# Flex_debugging.net
KiCad netlist of a schematic drawn in Altium Designer
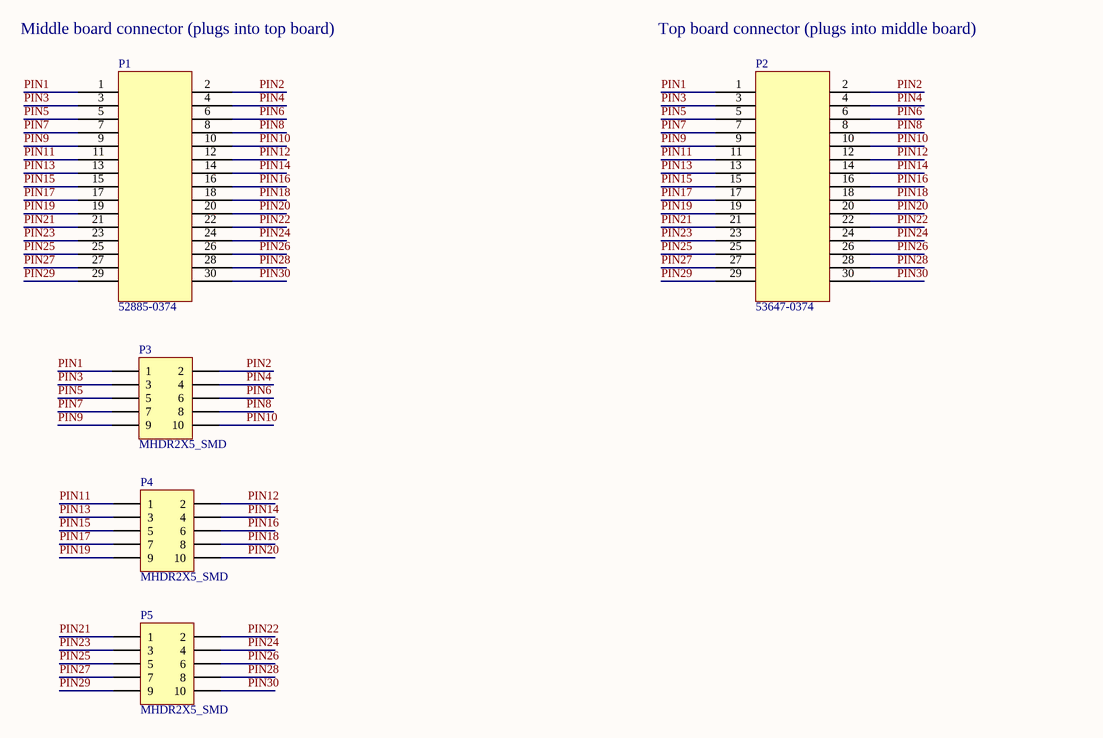
[diagram p0: Flex_debugging.SchDoc]

(export (version "E")
  (design (tool "Eeschema 10.0.6"))
  (components
    (comp (ref "P1")
      (value "52885-0374")
      (footprint "molex_52885-0374")
      (description "Molex 30-pin 0.635mm pitch receptacle connector")
      (libsource (lib "Hello") (part "molex_52885-0374"))
    )
    (comp (ref "P2")
      (value "53647-0374")
      (footprint "molex_53647-0374")
      (description "Molex 30-pin 0.635mm pitch plug connector")
      (libsource (lib "Hello") (part "molex_53647-0374"))
    )
    (comp (ref "P3")
      (value "MHDR2X5_SMD")
      (footprint "MHDR2X5_SMD")
      (description "Header, 10-Pin, Dual row SMD")
      (libsource (lib "Hello") (part "MHDR2X5_SMD"))
    )
    (comp (ref "P4")
      (value "MHDR2X5_SMD")
      (footprint "MHDR2X5_SMD")
      (description "Header, 10-Pin, Dual row SMD")
      (libsource (lib "Hello") (part "MHDR2X5_SMD"))
    )
    (comp (ref "P5")
      (value "MHDR2X5_SMD")
      (footprint "MHDR2X5_SMD")
      (description "Header, 10-Pin, Dual row SMD")
      (libsource (lib "Hello") (part "MHDR2X5_SMD"))
    )
  )
  (nets
    (net (code "1") (name "/PIN1") (class "Default")
      (node (ref "P1") (pin "1") (pintype "passive"))
      (node (ref "P2") (pin "1") (pintype "passive"))
      (node (ref "P3") (pin "1") (pinfunction "1_1") (pintype "passive"))
    )
    (net (code "2") (name "/PIN2") (class "Default")
      (node (ref "P1") (pin "2") (pintype "passive"))
      (node (ref "P2") (pin "2") (pintype "passive"))
      (node (ref "P3") (pin "2") (pinfunction "2_2") (pintype "passive"))
    )
    (net (code "3") (name "/PIN3") (class "Default")
      (node (ref "P1") (pin "3") (pintype "passive"))
      (node (ref "P2") (pin "3") (pintype "passive"))
      (node (ref "P3") (pin "3") (pinfunction "3_3") (pintype "passive"))
    )
    (net (code "4") (name "/PIN4") (class "Default")
      (node (ref "P1") (pin "4") (pintype "passive"))
      (node (ref "P2") (pin "4") (pintype "passive"))
      (node (ref "P3") (pin "4") (pinfunction "4_4") (pintype "passive"))
    )
    (net (code "5") (name "/PIN5") (class "Default")
      (node (ref "P1") (pin "5") (pintype "passive"))
      (node (ref "P2") (pin "5") (pintype "passive"))
      (node (ref "P3") (pin "5") (pinfunction "5_5") (pintype "passive"))
    )
    (net (code "6") (name "/PIN6") (class "Default")
      (node (ref "P1") (pin "6") (pintype "passive"))
      (node (ref "P2") (pin "6") (pintype "passive"))
      (node (ref "P3") (pin "6") (pinfunction "6_6") (pintype "passive"))
    )
    (net (code "7") (name "/PIN7") (class "Default")
      (node (ref "P1") (pin "7") (pintype "passive"))
      (node (ref "P2") (pin "7") (pintype "passive"))
      (node (ref "P3") (pin "7") (pinfunction "7_7") (pintype "passive"))
    )
    (net (code "8") (name "/PIN8") (class "Default")
      (node (ref "P1") (pin "8") (pintype "passive"))
      (node (ref "P2") (pin "8") (pintype "passive"))
      (node (ref "P3") (pin "8") (pinfunction "8_8") (pintype "passive"))
    )
    (net (code "9") (name "/PIN9") (class "Default")
      (node (ref "P1") (pin "9") (pintype "passive"))
      (node (ref "P2") (pin "9") (pintype "passive"))
      (node (ref "P3") (pin "9") (pinfunction "9_9") (pintype "passive"))
    )
    (net (code "10") (name "/PIN10") (class "Default")
      (node (ref "P1") (pin "10") (pintype "passive"))
      (node (ref "P2") (pin "10") (pintype "passive"))
      (node (ref "P3") (pin "10") (pinfunction "10_10") (pintype "passive"))
    )
    (net (code "11") (name "/PIN11") (class "Default")
      (node (ref "P1") (pin "11") (pintype "passive"))
      (node (ref "P2") (pin "11") (pintype "passive"))
      (node (ref "P4") (pin "1") (pinfunction "1_1") (pintype "passive"))
    )
    (net (code "12") (name "/PIN12") (class "Default")
      (node (ref "P1") (pin "12") (pintype "passive"))
      (node (ref "P2") (pin "12") (pintype "passive"))
      (node (ref "P4") (pin "2") (pinfunction "2_2") (pintype "passive"))
    )
    (net (code "13") (name "/PIN13") (class "Default")
      (node (ref "P1") (pin "13") (pintype "passive"))
      (node (ref "P2") (pin "13") (pintype "passive"))
      (node (ref "P4") (pin "3") (pinfunction "3_3") (pintype "passive"))
    )
    (net (code "14") (name "/PIN14") (class "Default")
      (node (ref "P1") (pin "14") (pintype "passive"))
      (node (ref "P2") (pin "14") (pintype "passive"))
      (node (ref "P4") (pin "4") (pinfunction "4_4") (pintype "passive"))
    )
    (net (code "15") (name "/PIN15") (class "Default")
      (node (ref "P1") (pin "15") (pintype "passive"))
      (node (ref "P2") (pin "15") (pintype "passive"))
      (node (ref "P4") (pin "5") (pinfunction "5_5") (pintype "passive"))
    )
    (net (code "16") (name "/PIN16") (class "Default")
      (node (ref "P1") (pin "16") (pintype "passive"))
      (node (ref "P2") (pin "16") (pintype "passive"))
      (node (ref "P4") (pin "6") (pinfunction "6_6") (pintype "passive"))
    )
    (net (code "17") (name "/PIN17") (class "Default")
      (node (ref "P1") (pin "17") (pintype "passive"))
      (node (ref "P2") (pin "17") (pintype "passive"))
      (node (ref "P4") (pin "7") (pinfunction "7_7") (pintype "passive"))
    )
    (net (code "18") (name "/PIN18") (class "Default")
      (node (ref "P1") (pin "18") (pintype "passive"))
      (node (ref "P2") (pin "18") (pintype "passive"))
      (node (ref "P4") (pin "8") (pinfunction "8_8") (pintype "passive"))
    )
    (net (code "19") (name "/PIN19") (class "Default")
      (node (ref "P1") (pin "19") (pintype "passive"))
      (node (ref "P2") (pin "19") (pintype "passive"))
      (node (ref "P4") (pin "9") (pinfunction "9_9") (pintype "passive"))
    )
    (net (code "20") (name "/PIN20") (class "Default")
      (node (ref "P1") (pin "20") (pintype "passive"))
      (node (ref "P2") (pin "20") (pintype "passive"))
      (node (ref "P4") (pin "10") (pinfunction "10_10") (pintype "passive"))
    )
    (net (code "21") (name "/PIN21") (class "Default")
      (node (ref "P1") (pin "21") (pintype "passive"))
      (node (ref "P2") (pin "21") (pintype "passive"))
      (node (ref "P5") (pin "1") (pinfunction "1_1") (pintype "passive"))
    )
    (net (code "22") (name "/PIN22") (class "Default")
      (node (ref "P1") (pin "22") (pintype "passive"))
      (node (ref "P2") (pin "22") (pintype "passive"))
      (node (ref "P5") (pin "2") (pinfunction "2_2") (pintype "passive"))
    )
    (net (code "23") (name "/PIN23") (class "Default")
      (node (ref "P1") (pin "23") (pintype "passive"))
      (node (ref "P2") (pin "23") (pintype "passive"))
      (node (ref "P5") (pin "3") (pinfunction "3_3") (pintype "passive"))
    )
    (net (code "24") (name "/PIN24") (class "Default")
      (node (ref "P1") (pin "24") (pintype "passive"))
      (node (ref "P2") (pin "24") (pintype "passive"))
      (node (ref "P5") (pin "4") (pinfunction "4_4") (pintype "passive"))
    )
    (net (code "25") (name "/PIN25") (class "Default")
      (node (ref "P1") (pin "25") (pintype "passive"))
      (node (ref "P2") (pin "25") (pintype "passive"))
      (node (ref "P5") (pin "5") (pinfunction "5_5") (pintype "passive"))
    )
    (net (code "26") (name "/PIN26") (class "Default")
      (node (ref "P1") (pin "26") (pintype "passive"))
      (node (ref "P2") (pin "26") (pintype "passive"))
      (node (ref "P5") (pin "6") (pinfunction "6_6") (pintype "passive"))
    )
    (net (code "27") (name "/PIN27") (class "Default")
      (node (ref "P1") (pin "27") (pintype "passive"))
      (node (ref "P2") (pin "27") (pintype "passive"))
      (node (ref "P5") (pin "7") (pinfunction "7_7") (pintype "passive"))
    )
    (net (code "28") (name "/PIN28") (class "Default")
      (node (ref "P1") (pin "28") (pintype "passive"))
      (node (ref "P2") (pin "28") (pintype "passive"))
      (node (ref "P5") (pin "8") (pinfunction "8_8") (pintype "passive"))
    )
    (net (code "29") (name "/PIN29") (class "Default")
      (node (ref "P1") (pin "29") (pintype "passive"))
      (node (ref "P2") (pin "29") (pintype "passive"))
      (node (ref "P5") (pin "9") (pinfunction "9_9") (pintype "passive"))
    )
    (net (code "30") (name "/PIN30") (class "Default")
      (node (ref "P1") (pin "30") (pintype "passive"))
      (node (ref "P2") (pin "30") (pintype "passive"))
      (node (ref "P5") (pin "10") (pinfunction "10_10") (pintype "passive"))
    )
  )
)
